# Sheet1.net
KiCad netlist of a schematic drawn in Altium Designer
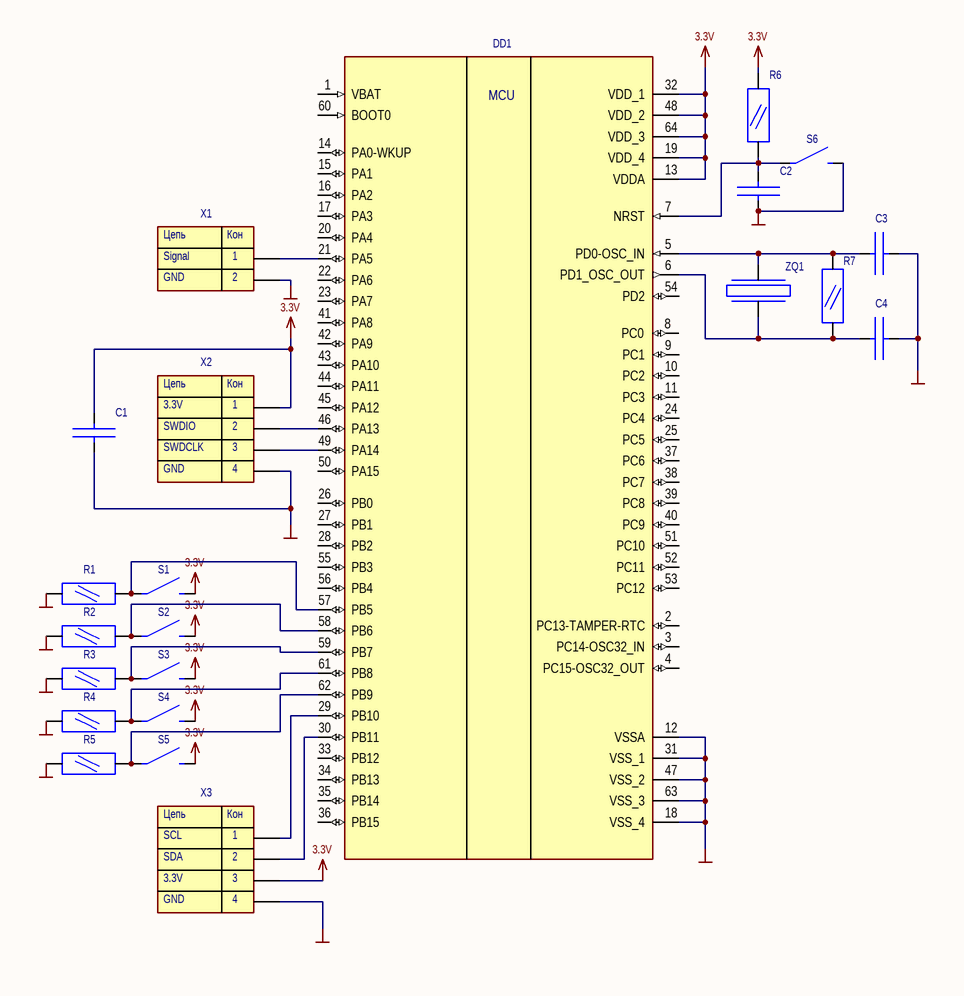
[diagram p0: Sheet1.SchDoc]

(export (version "E")
  (design (tool "Eeschema 10.0.6"))
  (components
    (comp (ref "C1") (value "condensator") (libsource (lib "Schlib1") (part "condensator")))
    (comp (ref "C2") (value "condensator") (libsource (lib "Schlib1") (part "condensator")))
    (comp (ref "C3") (value "condensator") (libsource (lib "Schlib1") (part "condensator")))
    (comp (ref "C4") (value "condensator") (libsource (lib "Schlib1") (part "condensator")))
    (comp (ref "DD1") (value "STM32F103RCT6") (libsource (lib "Schlib1") (part "STM32F103RCT6")))
    (comp (ref "R1") (value "resistor") (footprint "smd1206") (libsource (lib "Schlib1") (part "resistor")))
    (comp (ref "R2") (value "resistor") (footprint "smd1206") (libsource (lib "Schlib1") (part "resistor")))
    (comp (ref "R3") (value "resistor") (footprint "smd1206") (libsource (lib "Schlib1") (part "resistor")))
    (comp (ref "R4") (value "resistor") (footprint "smd1206") (libsource (lib "Schlib1") (part "resistor")))
    (comp (ref "R5") (value "resistor") (footprint "smd1206") (libsource (lib "Schlib1") (part "resistor")))
    (comp (ref "R6") (value "resistor") (footprint "smd1206") (libsource (lib "Schlib1") (part "resistor")))
    (comp (ref "R7") (value "resistor") (footprint "smd1206") (libsource (lib "Schlib1") (part "resistor")))
    (comp (ref "S1") (value "knopka") (libsource (lib "Schlib1") (part "knopka")))
    (comp (ref "S2") (value "knopka") (libsource (lib "Schlib1") (part "knopka")))
    (comp (ref "S3") (value "knopka") (libsource (lib "Schlib1") (part "knopka")))
    (comp (ref "S4") (value "knopka") (libsource (lib "Schlib1") (part "knopka")))
    (comp (ref "S5") (value "knopka") (libsource (lib "Schlib1") (part "knopka")))
    (comp (ref "S6") (value "knopka") (libsource (lib "Schlib1") (part "knopka")))
    (comp (ref "X1") (value "dac") (libsource (lib "Schlib1") (part "dac")))
    (comp (ref "X2") (value "SWD") (libsource (lib "Schlib1") (part "SWD")))
    (comp (ref "X3") (value "con_i2c_1") (libsource (lib "Schlib1") (part "con_i2c_1")))
    (comp (ref "ZQ1") (value "resonator") (libsource (lib "Schlib1") (part "resonator")))
  )
  (nets
    (net (code "1") (name "3.3V") (class "Default")
      (node (ref "C1") (pin "2") (pinfunction "2_2") (pintype "passive"))
      (node (ref "DD1") (pin "13") (pinfunction "VDDA_13") (pintype "power_in"))
      (node (ref "DD1") (pin "19") (pinfunction "VDD_4_19") (pintype "power_in"))
      (node (ref "DD1") (pin "32") (pinfunction "VDD_1_32") (pintype "power_in"))
      (node (ref "DD1") (pin "48") (pinfunction "VDD_2_48") (pintype "power_in"))
      (node (ref "DD1") (pin "64") (pinfunction "VDD_3_64") (pintype "power_in"))
      (node (ref "R6") (pin "2") (pinfunction "2_2") (pintype "passive"))
      (node (ref "S1") (pin "2") (pinfunction "2_2") (pintype "passive"))
      (node (ref "S2") (pin "2") (pinfunction "2_2") (pintype "passive"))
      (node (ref "S3") (pin "2") (pinfunction "2_2") (pintype "passive"))
      (node (ref "S4") (pin "2") (pinfunction "2_2") (pintype "passive"))
      (node (ref "S5") (pin "2") (pinfunction "2_2") (pintype "passive"))
      (node (ref "X2") (pin "1") (pinfunction "1_1") (pintype "passive"))
      (node (ref "X3") (pin "3") (pinfunction "3_3") (pintype "passive"))
    )
    (net (code "2") (name "GND") (class "Default")
      (node (ref "C1") (pin "1") (pinfunction "1_1") (pintype "passive"))
      (node (ref "C2") (pin "1") (pinfunction "1_1") (pintype "passive"))
      (node (ref "C3") (pin "2") (pinfunction "2_2") (pintype "passive"))
      (node (ref "C4") (pin "2") (pinfunction "2_2") (pintype "passive"))
      (node (ref "DD1") (pin "12") (pinfunction "VSSA_12") (pintype "power_in"))
      (node (ref "DD1") (pin "18") (pinfunction "VSS_4_18") (pintype "power_in"))
      (node (ref "DD1") (pin "31") (pinfunction "VSS_1_31") (pintype "power_in"))
      (node (ref "DD1") (pin "47") (pinfunction "VSS_2_47") (pintype "power_in"))
      (node (ref "DD1") (pin "63") (pinfunction "VSS_3_63") (pintype "power_in"))
      (node (ref "R1") (pin "1") (pinfunction "1_1") (pintype "passive"))
      (node (ref "R2") (pin "1") (pinfunction "1_1") (pintype "passive"))
      (node (ref "R3") (pin "1") (pinfunction "1_1") (pintype "passive"))
      (node (ref "R4") (pin "1") (pinfunction "1_1") (pintype "passive"))
      (node (ref "R5") (pin "1") (pinfunction "1_1") (pintype "passive"))
      (node (ref "S6") (pin "2") (pinfunction "2_2") (pintype "passive"))
      (node (ref "X1") (pin "2") (pinfunction "2_2") (pintype "passive"))
      (node (ref "X2") (pin "4") (pinfunction "4_4") (pintype "passive"))
      (node (ref "X3") (pin "4") (pinfunction "4_4") (pintype "passive"))
    )
    (net (code "3") (name "Net-(DD1-NRST)") (class "Default")
      (node (ref "C2") (pin "2") (pinfunction "2_2") (pintype "passive"))
      (node (ref "DD1") (pin "7") (pinfunction "NRST_7") (pintype "input"))
      (node (ref "R6") (pin "1") (pinfunction "1_1") (pintype "passive"))
      (node (ref "S6") (pin "1") (pinfunction "1_1") (pintype "passive"))
    )
    (net (code "4") (name "Net-(DD1-PA5)") (class "Default")
      (node (ref "DD1") (pin "21") (pinfunction "PA5_21") (pintype "bidirectional"))
      (node (ref "X1") (pin "1") (pinfunction "1_1") (pintype "passive"))
    )
    (net (code "5") (name "Net-(DD1-PA13)") (class "Default")
      (node (ref "DD1") (pin "46") (pinfunction "PA13_46") (pintype "bidirectional"))
      (node (ref "X2") (pin "2") (pinfunction "2_2") (pintype "passive"))
    )
    (net (code "6") (name "Net-(DD1-PA14)") (class "Default")
      (node (ref "DD1") (pin "49") (pinfunction "PA14_49") (pintype "bidirectional"))
      (node (ref "X2") (pin "3") (pinfunction "3_3") (pintype "passive"))
    )
    (net (code "7") (name "Net-(DD1-PB5)") (class "Default")
      (node (ref "DD1") (pin "57") (pinfunction "PB5_57") (pintype "bidirectional"))
      (node (ref "R1") (pin "2") (pinfunction "2_2") (pintype "passive"))
      (node (ref "S1") (pin "1") (pinfunction "1_1") (pintype "passive"))
    )
    (net (code "8") (name "Net-(DD1-PB6)") (class "Default")
      (node (ref "DD1") (pin "58") (pinfunction "PB6_58") (pintype "bidirectional"))
      (node (ref "R2") (pin "2") (pinfunction "2_2") (pintype "passive"))
      (node (ref "S2") (pin "1") (pinfunction "1_1") (pintype "passive"))
    )
    (net (code "9") (name "Net-(DD1-PB7)") (class "Default")
      (node (ref "DD1") (pin "59") (pinfunction "PB7_59") (pintype "bidirectional"))
      (node (ref "R3") (pin "2") (pinfunction "2_2") (pintype "passive"))
      (node (ref "S3") (pin "1") (pinfunction "1_1") (pintype "passive"))
    )
    (net (code "10") (name "Net-(DD1-PB8)") (class "Default")
      (node (ref "DD1") (pin "61") (pinfunction "PB8_61") (pintype "bidirectional"))
      (node (ref "R4") (pin "2") (pinfunction "2_2") (pintype "passive"))
      (node (ref "S4") (pin "1") (pinfunction "1_1") (pintype "passive"))
    )
    (net (code "11") (name "Net-(DD1-PB9)") (class "Default")
      (node (ref "DD1") (pin "62") (pinfunction "PB9_62") (pintype "bidirectional"))
      (node (ref "R5") (pin "2") (pinfunction "2_2") (pintype "passive"))
      (node (ref "S5") (pin "1") (pinfunction "1_1") (pintype "passive"))
    )
    (net (code "12") (name "Net-(DD1-PB10)") (class "Default")
      (node (ref "DD1") (pin "29") (pinfunction "PB10_29") (pintype "bidirectional"))
      (node (ref "X3") (pin "1") (pinfunction "1_1") (pintype "passive"))
    )
    (net (code "13") (name "Net-(DD1-PB11)") (class "Default")
      (node (ref "DD1") (pin "30") (pinfunction "PB11_30") (pintype "bidirectional"))
      (node (ref "X3") (pin "2") (pinfunction "2_2") (pintype "passive"))
    )
    (net (code "14") (name "Net-(DD1-PD0-OSC_IN)") (class "Default")
      (node (ref "C3") (pin "1") (pinfunction "1_1") (pintype "passive"))
      (node (ref "DD1") (pin "5") (pinfunction "PD0-OSC_IN_5") (pintype "input"))
      (node (ref "R7") (pin "2") (pinfunction "2_2") (pintype "passive"))
      (node (ref "ZQ1") (pin "1") (pinfunction "1_1") (pintype "passive"))
    )
    (net (code "15") (name "Net-(DD1-PD1_OSC_OUT)") (class "Default")
      (node (ref "C4") (pin "1") (pinfunction "1_1") (pintype "passive"))
      (node (ref "DD1") (pin "6") (pinfunction "PD1_OSC_OUT_6") (pintype "output"))
      (node (ref "R7") (pin "1") (pinfunction "1_1") (pintype "passive"))
      (node (ref "ZQ1") (pin "2") (pinfunction "2_2") (pintype "passive"))
    )
    (net (code "16") (name "unconnected-(DD1-BOOT0-Pad60)") (class "Default")
      (node (ref "DD1") (pin "60") (pinfunction "BOOT0_60") (pintype "input"))
    )
    (net (code "17") (name "unconnected-(DD1-PA0-WKUP-Pad14)") (class "Default")
      (node (ref "DD1") (pin "14") (pinfunction "PA0-WKUP_14") (pintype "bidirectional"))
    )
    (net (code "18") (name "unconnected-(DD1-PA1-Pad15)") (class "Default")
      (node (ref "DD1") (pin "15") (pinfunction "PA1_15") (pintype "bidirectional"))
    )
    (net (code "19") (name "unconnected-(DD1-PA2-Pad16)") (class "Default")
      (node (ref "DD1") (pin "16") (pinfunction "PA2_16") (pintype "bidirectional"))
    )
    (net (code "20") (name "unconnected-(DD1-PA3-Pad17)") (class "Default")
      (node (ref "DD1") (pin "17") (pinfunction "PA3_17") (pintype "bidirectional"))
    )
    (net (code "21") (name "unconnected-(DD1-PA4-Pad20)") (class "Default")
      (node (ref "DD1") (pin "20") (pinfunction "PA4_20") (pintype "bidirectional"))
    )
    (net (code "22") (name "unconnected-(DD1-PA6-Pad22)") (class "Default")
      (node (ref "DD1") (pin "22") (pinfunction "PA6_22") (pintype "bidirectional"))
    )
    (net (code "23") (name "unconnected-(DD1-PA7-Pad23)") (class "Default")
      (node (ref "DD1") (pin "23") (pinfunction "PA7_23") (pintype "bidirectional"))
    )
    (net (code "24") (name "unconnected-(DD1-PA8-Pad41)") (class "Default")
      (node (ref "DD1") (pin "41") (pinfunction "PA8_41") (pintype "bidirectional"))
    )
    (net (code "25") (name "unconnected-(DD1-PA9-Pad42)") (class "Default")
      (node (ref "DD1") (pin "42") (pinfunction "PA9_42") (pintype "bidirectional"))
    )
    (net (code "26") (name "unconnected-(DD1-PA10-Pad43)") (class "Default")
      (node (ref "DD1") (pin "43") (pinfunction "PA10_43") (pintype "bidirectional"))
    )
    (net (code "27") (name "unconnected-(DD1-PA11-Pad44)") (class "Default")
      (node (ref "DD1") (pin "44") (pinfunction "PA11_44") (pintype "bidirectional"))
    )
    (net (code "28") (name "unconnected-(DD1-PA12-Pad45)") (class "Default")
      (node (ref "DD1") (pin "45") (pinfunction "PA12_45") (pintype "bidirectional"))
    )
    (net (code "29") (name "unconnected-(DD1-PA15-Pad50)") (class "Default")
      (node (ref "DD1") (pin "50") (pinfunction "PA15_50") (pintype "bidirectional"))
    )
    (net (code "30") (name "unconnected-(DD1-PB0-Pad26)") (class "Default")
      (node (ref "DD1") (pin "26") (pinfunction "PB0_26") (pintype "bidirectional"))
    )
    (net (code "31") (name "unconnected-(DD1-PB1-Pad27)") (class "Default")
      (node (ref "DD1") (pin "27") (pinfunction "PB1_27") (pintype "bidirectional"))
    )
    (net (code "32") (name "unconnected-(DD1-PB2-Pad28)") (class "Default")
      (node (ref "DD1") (pin "28") (pinfunction "PB2_28") (pintype "bidirectional"))
    )
    (net (code "33") (name "unconnected-(DD1-PB3-Pad55)") (class "Default")
      (node (ref "DD1") (pin "55") (pinfunction "PB3_55") (pintype "bidirectional"))
    )
    (net (code "34") (name "unconnected-(DD1-PB4-Pad56)") (class "Default")
      (node (ref "DD1") (pin "56") (pinfunction "PB4_56") (pintype "bidirectional"))
    )
    (net (code "35") (name "unconnected-(DD1-PB12-Pad33)") (class "Default")
      (node (ref "DD1") (pin "33") (pinfunction "PB12_33") (pintype "bidirectional"))
    )
    (net (code "36") (name "unconnected-(DD1-PB13-Pad34)") (class "Default")
      (node (ref "DD1") (pin "34") (pinfunction "PB13_34") (pintype "bidirectional"))
    )
    (net (code "37") (name "unconnected-(DD1-PB14-Pad35)") (class "Default")
      (node (ref "DD1") (pin "35") (pinfunction "PB14_35") (pintype "bidirectional"))
    )
    (net (code "38") (name "unconnected-(DD1-PB15-Pad36)") (class "Default")
      (node (ref "DD1") (pin "36") (pinfunction "PB15_36") (pintype "bidirectional"))
    )
    (net (code "39") (name "unconnected-(DD1-PC0-Pad8)") (class "Default")
      (node (ref "DD1") (pin "8") (pinfunction "PC0_8") (pintype "bidirectional"))
    )
    (net (code "40") (name "unconnected-(DD1-PC1-Pad9)") (class "Default")
      (node (ref "DD1") (pin "9") (pinfunction "PC1_9") (pintype "bidirectional"))
    )
    (net (code "41") (name "unconnected-(DD1-PC2-Pad10)") (class "Default")
      (node (ref "DD1") (pin "10") (pinfunction "PC2_10") (pintype "bidirectional"))
    )
    (net (code "42") (name "unconnected-(DD1-PC3-Pad11)") (class "Default")
      (node (ref "DD1") (pin "11") (pinfunction "PC3_11") (pintype "bidirectional"))
    )
    (net (code "43") (name "unconnected-(DD1-PC4-Pad24)") (class "Default")
      (node (ref "DD1") (pin "24") (pinfunction "PC4_24") (pintype "bidirectional"))
    )
    (net (code "44") (name "unconnected-(DD1-PC5-Pad25)") (class "Default")
      (node (ref "DD1") (pin "25") (pinfunction "PC5_25") (pintype "bidirectional"))
    )
    (net (code "45") (name "unconnected-(DD1-PC6-Pad37)") (class "Default")
      (node (ref "DD1") (pin "37") (pinfunction "PC6_37") (pintype "bidirectional"))
    )
    (net (code "46") (name "unconnected-(DD1-PC7-Pad38)") (class "Default")
      (node (ref "DD1") (pin "38") (pinfunction "PC7_38") (pintype "bidirectional"))
    )
    (net (code "47") (name "unconnected-(DD1-PC8-Pad39)") (class "Default")
      (node (ref "DD1") (pin "39") (pinfunction "PC8_39") (pintype "bidirectional"))
    )
    (net (code "48") (name "unconnected-(DD1-PC9-Pad40)") (class "Default")
      (node (ref "DD1") (pin "40") (pinfunction "PC9_40") (pintype "bidirectional"))
    )
    (net (code "49") (name "unconnected-(DD1-PC10-Pad51)") (class "Default")
      (node (ref "DD1") (pin "51") (pinfunction "PC10_51") (pintype "bidirectional"))
    )
    (net (code "50") (name "unconnected-(DD1-PC11-Pad52)") (class "Default")
      (node (ref "DD1") (pin "52") (pinfunction "PC11_52") (pintype "bidirectional"))
    )
    (net (code "51") (name "unconnected-(DD1-PC12-Pad53)") (class "Default")
      (node (ref "DD1") (pin "53") (pinfunction "PC12_53") (pintype "bidirectional"))
    )
    (net (code "52") (name "unconnected-(DD1-PC13-TAMPER-RTC-Pad2)") (class "Default")
      (node (ref "DD1") (pin "2") (pinfunction "PC13-TAMPER-RTC_2") (pintype "bidirectional"))
    )
    (net (code "53") (name "unconnected-(DD1-PC14-OSC32_IN-Pad3)") (class "Default")
      (node (ref "DD1") (pin "3") (pinfunction "PC14-OSC32_IN_3") (pintype "bidirectional"))
    )
    (net (code "54") (name "unconnected-(DD1-PC15-OSC32_OUT-Pad4)") (class "Default")
      (node (ref "DD1") (pin "4") (pinfunction "PC15-OSC32_OUT_4") (pintype "bidirectional"))
    )
    (net (code "55") (name "unconnected-(DD1-PD2-Pad54)") (class "Default")
      (node (ref "DD1") (pin "54") (pinfunction "PD2_54") (pintype "bidirectional"))
    )
    (net (code "56") (name "unconnected-(DD1-VBAT-Pad1)") (class "Default")
      (node (ref "DD1") (pin "1") (pinfunction "VBAT_1") (pintype "input"))
    )
  )
)
